# H15R00.net
KiCad netlist of a schematic drawn in EAGLE
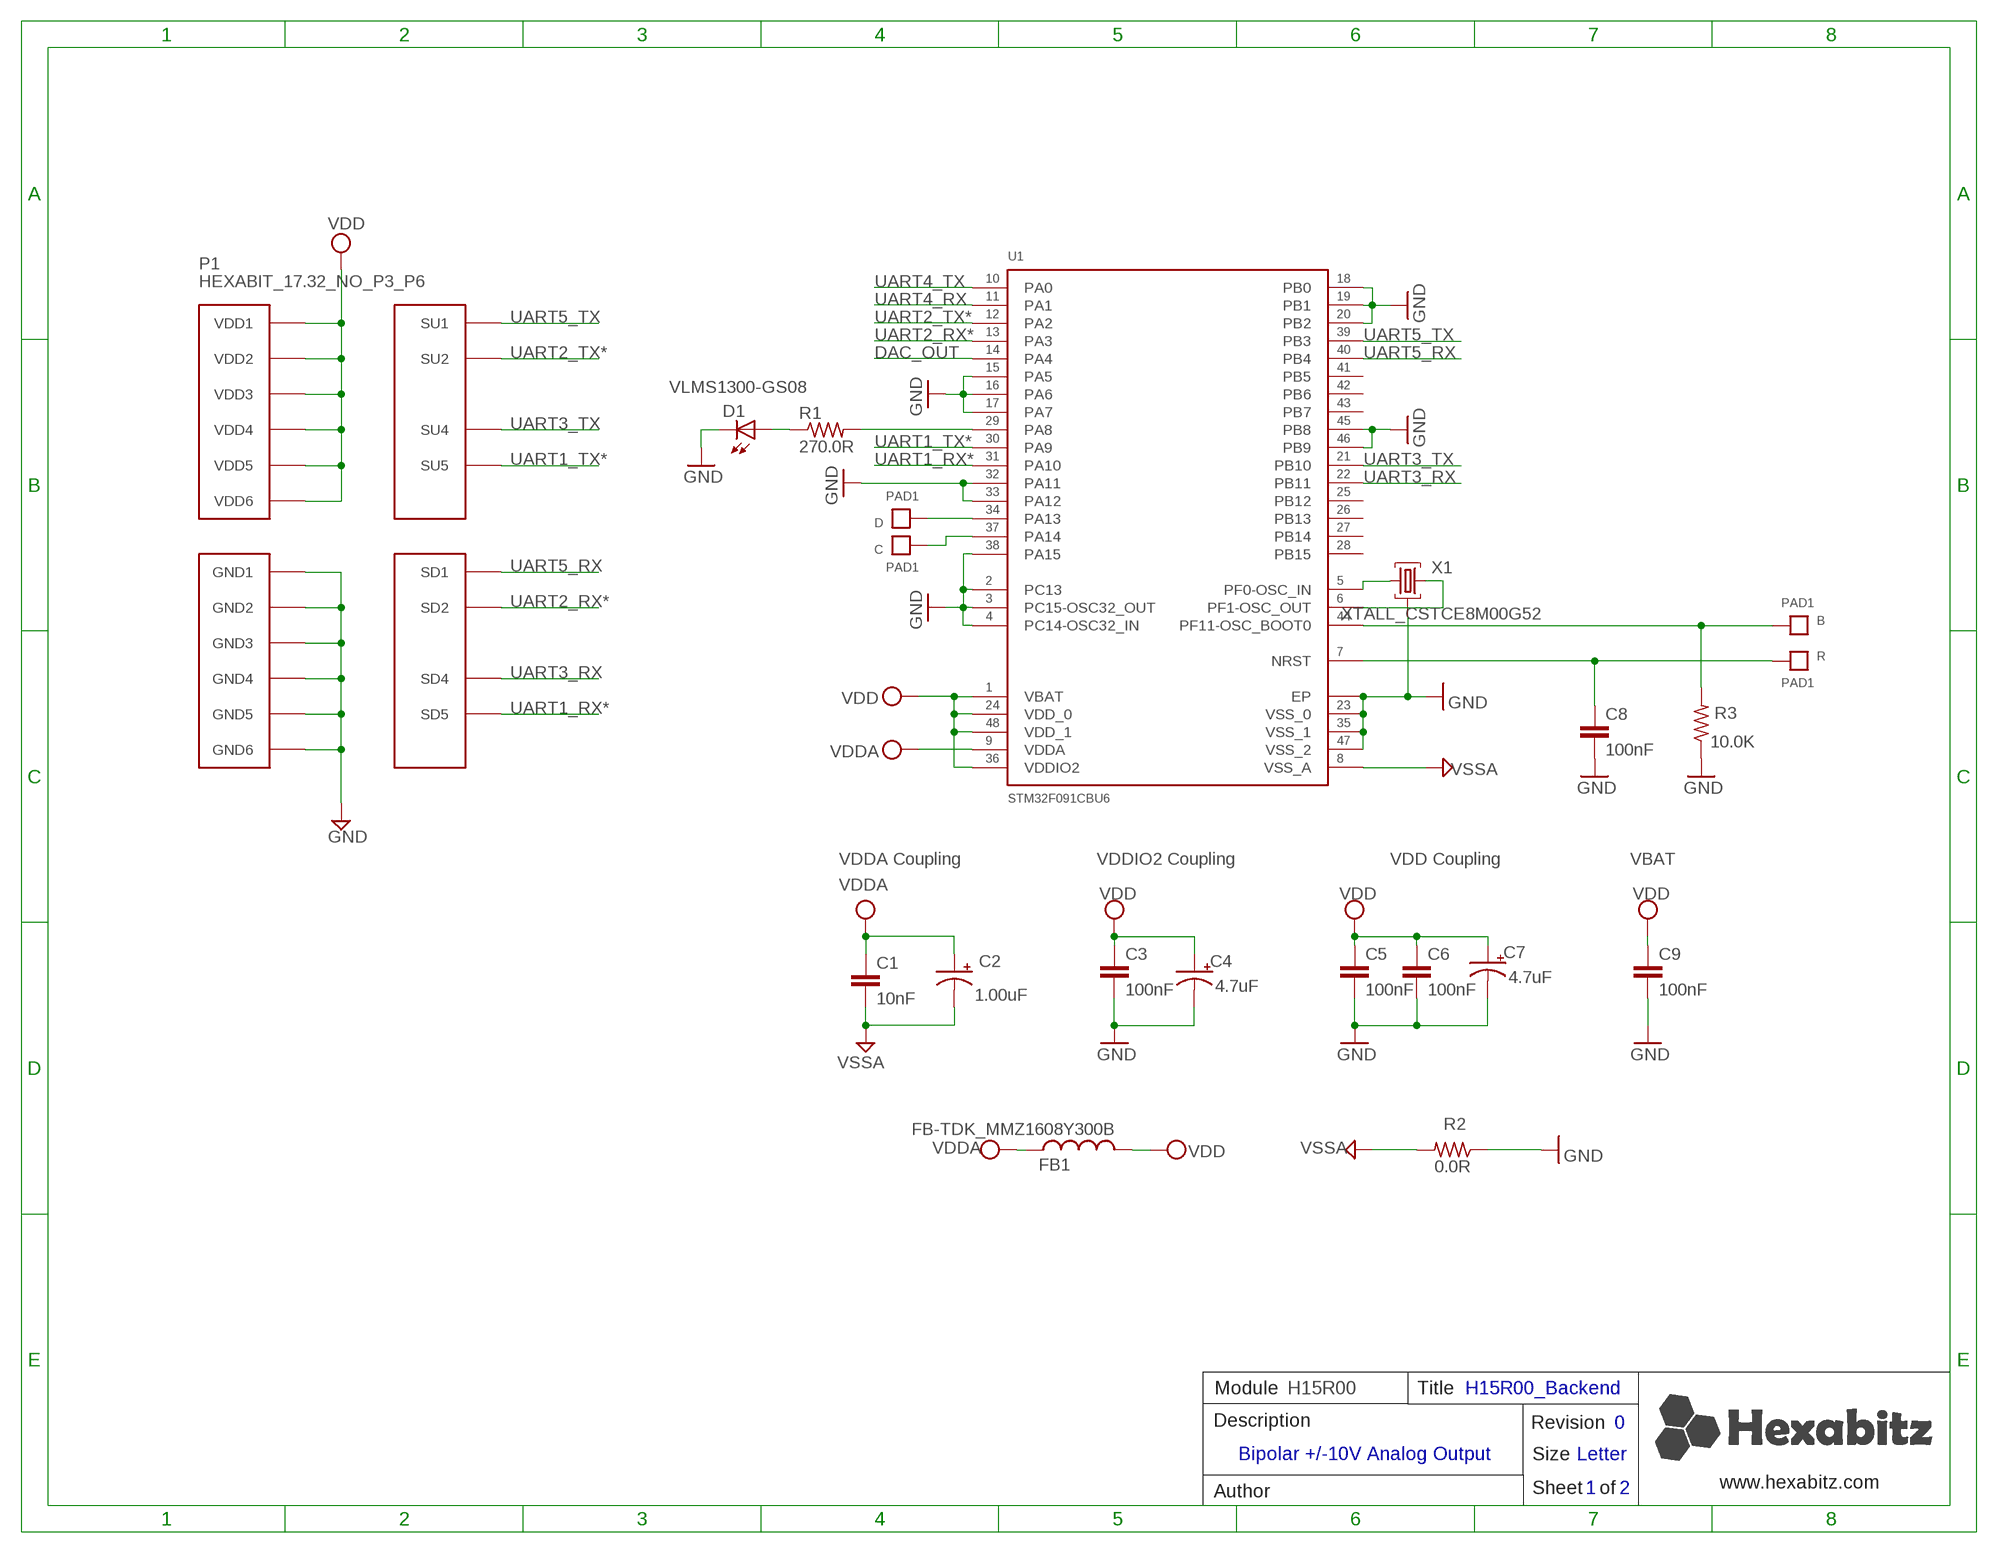
[diagram p0: schematic, sheet 1]
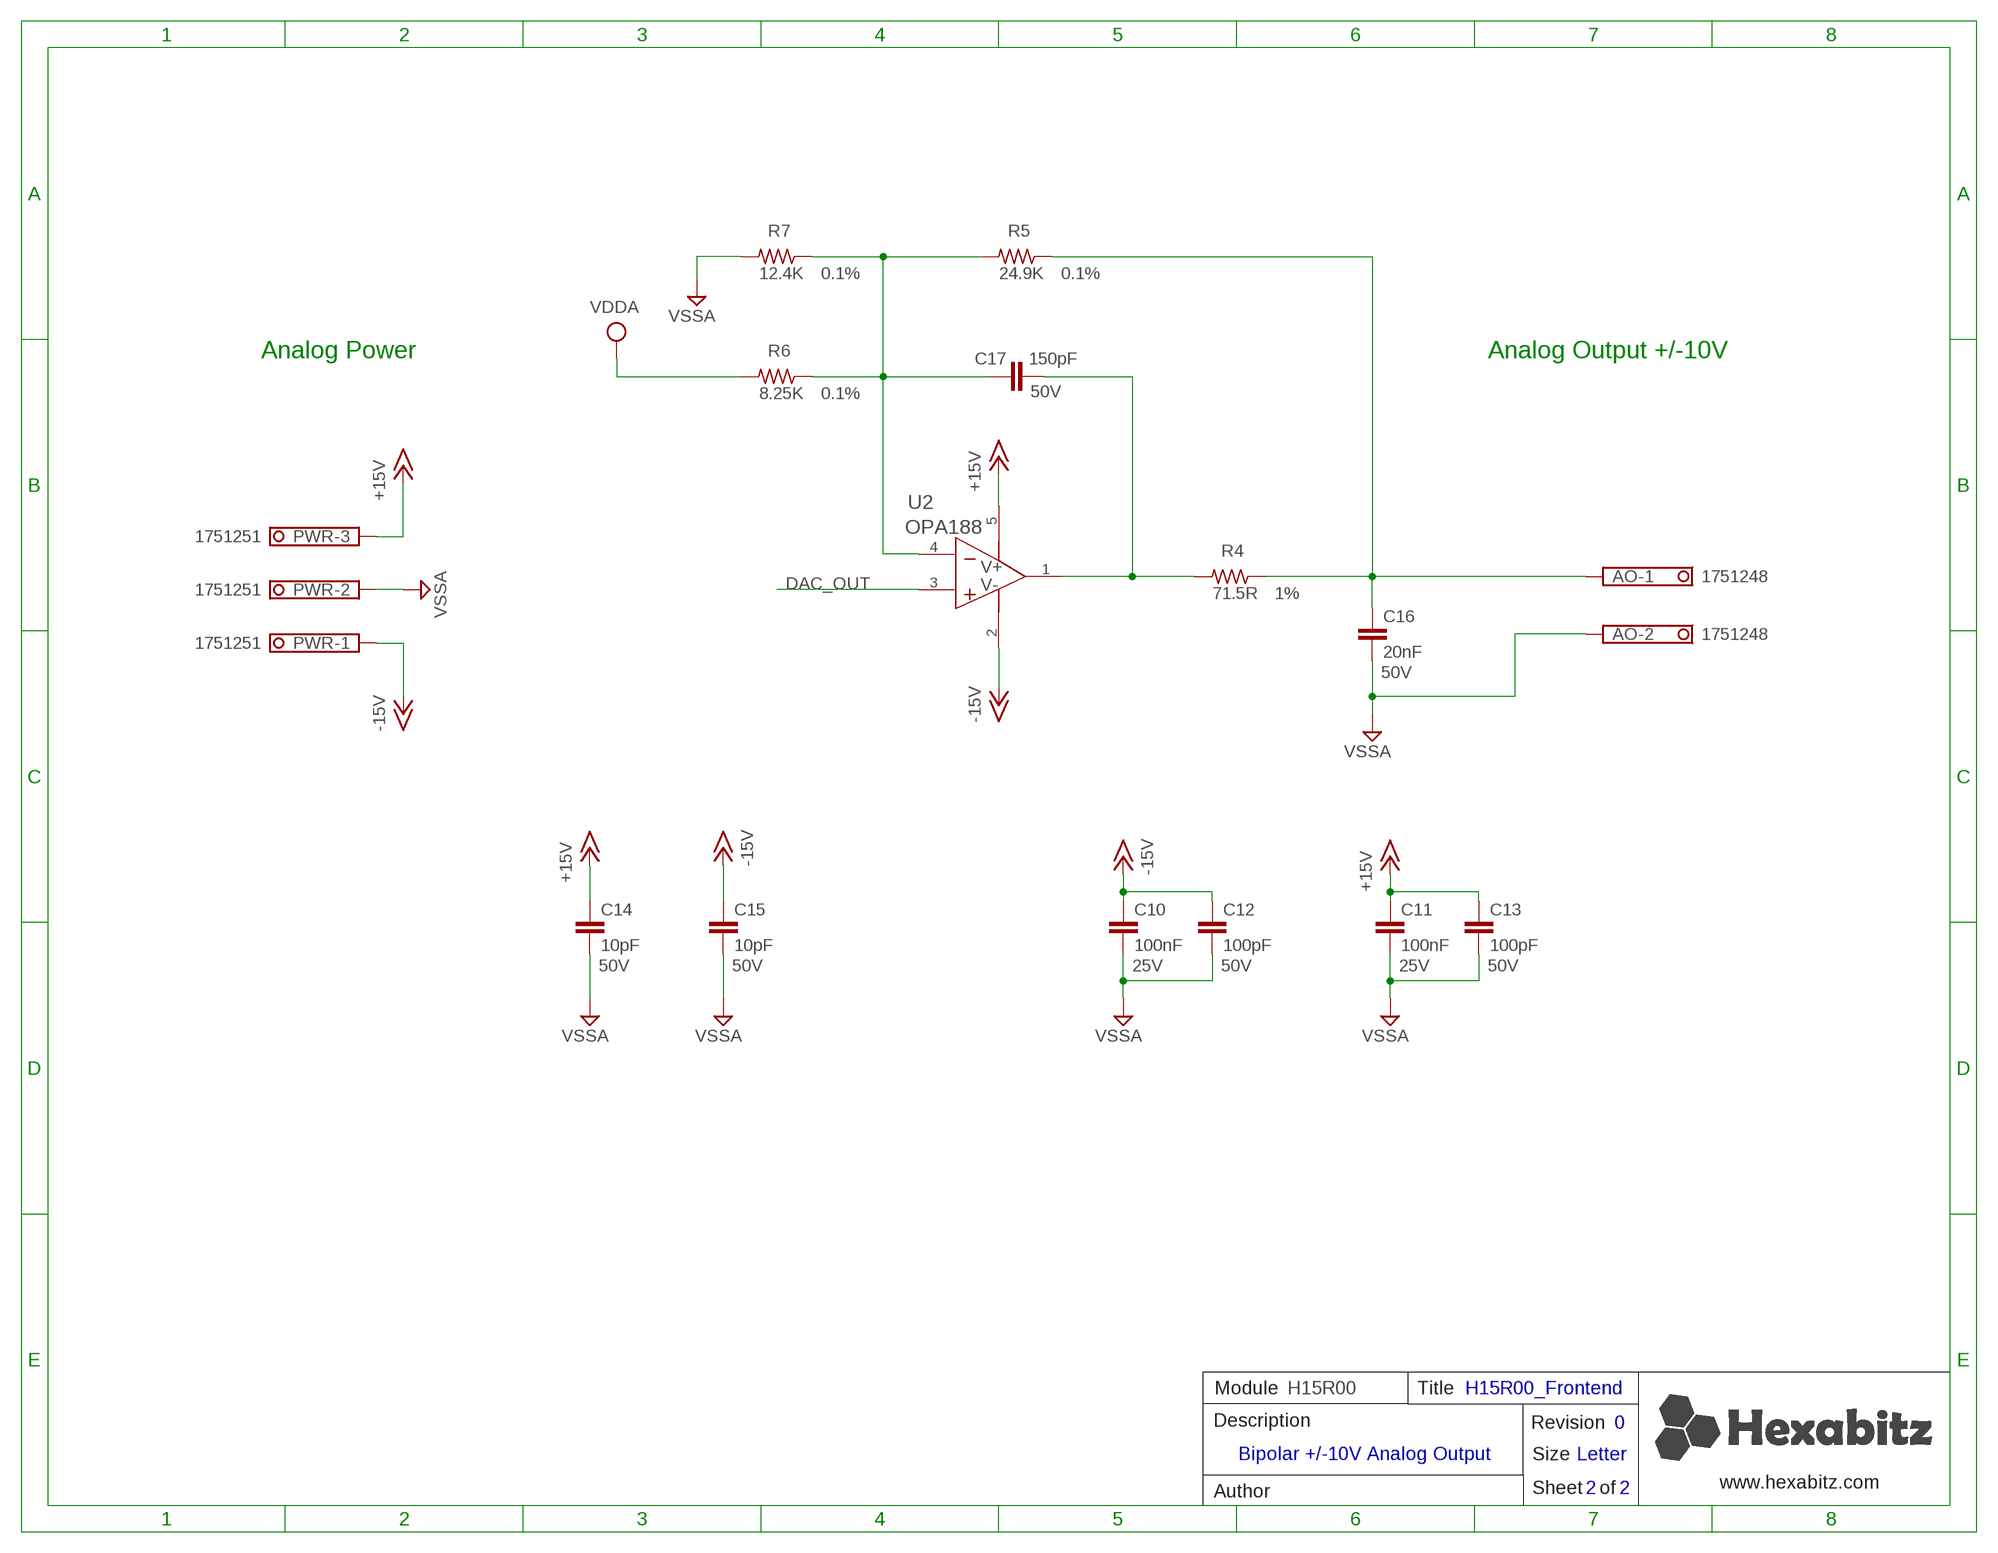
[diagram p1: schematic, sheet 2]

(export (version "E")
  (design (tool "Eeschema 10.0.6"))
  (components
    (comp (ref "AO")
      (value "1751248")
      (footprint "eagle-import:CON-PHOENIX-350_1751248")
      (fields
        (field (name "MPN") "1751248")
        (field (name "MFN") "Phoenix Contact")
        (field (name "OCTOPART_URL") "https://octopart.com/1751248-phoenix+contact-31334?r=sp&s=dfbEyNHiQNetUL69ahOrPQ")
      )
      (libsource (lib "eagle-import") (part "CON-PHOENIX-350_1751248"))
    )
    (comp (ref "C10")
      (value "100nF")
      (footprint "eagle-import:C-0603")
      (fields
        (field (name "CAPACITANCE") "100nF")
        (field (name "MFN") "Murata")
        (field (name "MPN") "GRM188R71E104KA01D")
        (field (name "OCTOPART_URL") "https://octopart.com/grm188r71e104ka01d-murata-196239?r=sp&s=9Sa0iYM-THq9pjXKXbxryA")
        (field (name "TOLERANCE") "10%")
        (field (name "VOLTAGE_RATING") "25V")
      )
      (libsource (lib "eagle-import") (part "C-0603"))
    )
    (comp (ref "C11")
      (value "100nF")
      (footprint "eagle-import:C-0603")
      (fields
        (field (name "CAPACITANCE") "100nF")
        (field (name "MFN") "Murata")
        (field (name "MPN") "GRM188R71E104KA01D")
        (field (name "OCTOPART_URL") "https://octopart.com/grm188r71e104ka01d-murata-196239?r=sp&s=9Sa0iYM-THq9pjXKXbxryA")
        (field (name "TOLERANCE") "10%")
        (field (name "VOLTAGE_RATING") "25V")
      )
      (libsource (lib "eagle-import") (part "C-0603"))
    )
    (comp (ref "C12")
      (value "100pF")
      (footprint "eagle-import:C-0603")
      (fields
        (field (name "CAPACITANCE") "100pF")
        (field (name "MFN") "Avx")
        (field (name "MPN") "06035A101JAT2A")
        (field (name "OCTOPART_URL") "https://octopart.com/06035a101jat2a-avx-55386344?r=sp&s=OWJQ2Zm8S2q0g8RSQtFoSw")
        (field (name "TOLERANCE") "5%")
        (field (name "VOLTAGE_RATING") "50V")
      )
      (libsource (lib "eagle-import") (part "C-0603"))
    )
    (comp (ref "C13")
      (value "100pF")
      (footprint "eagle-import:C-0603")
      (fields
        (field (name "CAPACITANCE") "100pF")
        (field (name "MFN") "Avx")
        (field (name "MPN") "06035A101JAT2A")
        (field (name "OCTOPART_URL") "https://octopart.com/06035a101jat2a-avx-55386344?r=sp&s=OWJQ2Zm8S2q0g8RSQtFoSw")
        (field (name "TOLERANCE") "5%")
        (field (name "VOLTAGE_RATING") "50V")
      )
      (libsource (lib "eagle-import") (part "C-0603"))
    )
    (comp (ref "C14")
      (value "10pF")
      (footprint "eagle-import:C-0603")
      (fields
        (field (name "CAPACITANCE") "10pF")
        (field (name "MFN") "Murata")
        (field (name "MPN") "GRM1885C1H100JA01D")
        (field (name "OCTOPART_URL") "https://octopart.com/grm1885c1h100ja01d-murata-196121?r=sp&s=M0doikvzQymn4ajEe0ihSw")
        (field (name "TOLERANCE") "5%")
        (field (name "VOLTAGE_RATING") "50V")
      )
      (libsource (lib "eagle-import") (part "C-0603"))
    )
    (comp (ref "C15")
      (value "10pF")
      (footprint "eagle-import:C-0603")
      (fields
        (field (name "CAPACITANCE") "10pF")
        (field (name "MFN") "Murata")
        (field (name "MPN") "GRM1885C1H100JA01D")
        (field (name "OCTOPART_URL") "https://octopart.com/grm1885c1h100ja01d-murata-196121?r=sp&s=M0doikvzQymn4ajEe0ihSw")
        (field (name "TOLERANCE") "5%")
        (field (name "VOLTAGE_RATING") "50V")
      )
      (libsource (lib "eagle-import") (part "C-0603"))
    )
    (comp (ref "C16")
      (value "20nF")
      (footprint "eagle-import:C-0603")
      (fields
        (field (name "CAPACITANCE") "20nF")
        (field (name "MFN") "Samsung")
        (field (name "MPN") "CL10B203KB8NNNC")
        (field (name "OCTOPART_URL") "https://octopart.com/cl10b203kb8nnnc-samsung-19831635?r=sp&s=OBY_pk9VR_mJ3Hxg4Ft1_g")
        (field (name "TOLERANCE") "10%")
        (field (name "VOLTAGE_RATING") "50V")
      )
      (libsource (lib "eagle-import") (part "C-0603"))
    )
    (comp (ref "C17")
      (value "150pF")
      (footprint "eagle-import:C-0603")
      (fields
        (field (name "CAPACITANCE") "150pF")
        (field (name "MFN") "TDK")
        (field (name "MPN") "C1608C0G1H151F080AA")
        (field (name "OCTOPART_URL") "https://octopart.com/c1608c0g1h151f080aa-tdk-26013419?r=sp&s=gUiTfpbJT1mAyA8NJ0XI8Q")
        (field (name "TOLERANCE") "1%")
        (field (name "VOLTAGE_RATING") "50V")
      )
      (libsource (lib "eagle-import") (part "C-0603"))
    )
    (comp (ref "PWR")
      (value "1751251")
      (footprint "eagle-import:1751251")
      (fields
        (field (name "MPN") "1751251")
        (field (name "MFN") "Phoenix Contact")
        (field (name "OCTOPART_URL") "https://octopart.com/1751251-phoenix+contact-36473?r=sp&s=9M0VWNoHTyq04j3qI6lQOQ")
      )
      (libsource (lib "eagle-import") (part "1751251"))
    )
    (comp (ref "R4")
      (value "71.5R")
      (footprint "eagle-import:R-0603")
      (fields
        (field (name "MFN") "Panasonic")
        (field (name "MPN") "ERJ-3EKF71R5V")
        (field (name "OCTOPART_URL") "https://octopart.com/erj-3ekf71r5v-panasonic-55421901?r=sp&s=JXFkVIq0Td2PcEUj2-UrKA")
        (field (name "RESISTANCE") "71.5 Ohm")
        (field (name "TOLERANCE") "1%")
      )
      (libsource (lib "eagle-import") (part "R-0603"))
    )
    (comp (ref "R5")
      (value "24.9K")
      (footprint "eagle-import:R-0603")
      (fields
        (field (name "MFN") "Panasonic")
        (field (name "MPN") "ERA-3AEB2492V")
        (field (name "OCTOPART_URL") "https://octopart.com/era-3aeb2492v-panasonic-14412272?r=sp&s=tIguNO2DQ02PU7gq6_vEIQ")
        (field (name "RESISTANCE") "24.9 kOhm")
        (field (name "TOLERANCE") "0.1%")
      )
      (libsource (lib "eagle-import") (part "R-0603"))
    )
    (comp (ref "R6")
      (value "8.25K")
      (footprint "eagle-import:R-0603")
      (fields
        (field (name "MFN") "Panasonic")
        (field (name "MPN") "ERA-3AEB8251V")
        (field (name "OCTOPART_URL") "https://octopart.com/era-3aeb8251v-panasonic-55477301?r=sp&s=p46abNa6QO-wGnrush-PUA")
        (field (name "RESISTANCE") "8.25 kOhm")
        (field (name "TOLERANCE") "0.1%")
      )
      (libsource (lib "eagle-import") (part "R-0603"))
    )
    (comp (ref "R7")
      (value "12.4K")
      (footprint "eagle-import:R-0603")
      (fields
        (field (name "MFN") "Panasonic")
        (field (name "MPN") "ERA-3AEB1242V")
        (field (name "OCTOPART_URL") "https://octopart.com/era-3aeb1242v-panasonic-55639351?r=sp&s=K0xQjqOwSGaT1tqbXnh0hg")
        (field (name "RESISTANCE") "12.4 kOhm")
        (field (name "TOLERANCE") "0.1%")
      )
      (libsource (lib "eagle-import") (part "R-0603"))
    )
    (comp (ref "U2")
      (value "OPA188")
      (footprint "eagle-import:DBV0005A_N")
      (fields
        (field (name "ALTERNATE_PARTNUMBER") "OPA188AIDBVT")
        (field (name "MANUFACTURER") "Texas Instruments")
        (field (name "MPN") "OPA188AIDBVR")
      )
      (libsource (lib "eagle-import") (part "OPA188AIDBVR"))
    )
    (comp (ref "B")
      (value "PAD1")
      (footprint "eagle-import:PAD1")
      (libsource (lib "eagle-import") (part "PAD1"))
    )
    (comp (ref "C")
      (value "PAD1")
      (footprint "eagle-import:PAD1")
      (libsource (lib "eagle-import") (part "PAD1"))
    )
    (comp (ref "C1")
      (value "10nF")
      (footprint "eagle-import:C-0603")
      (fields
        (field (name "CAPACITANCE") "10nF")
        (field (name "MFN") "KEMET")
        (field (name "MPN") "C0603C103K5RACTU")
        (field (name "OCTOPART_URL") "https://octopart.com/c0603c103k5ractu-kemet-133094?r=sp&s=R_iPBxLnSmGqhkU2rIMFpg")
        (field (name "TOLERANCE") "10%")
        (field (name "VOLTAGE_RATING") "50V")
      )
      (libsource (lib "eagle-import") (part "C-0603"))
    )
    (comp (ref "C2")
      (value "1.00uF")
      (footprint "eagle-import:C-0805-POL")
      (fields
        (field (name "CAPACITANCE") "1.00uF")
        (field (name "MFN") "Yageo")
        (field (name "MPN") "CC0805KKX7R7BB105")
        (field (name "OCTOPART_URL") "https://octopart.com/cc0805kkx7r7bb105-yageo-8376555?r=sp&s=YKl1wwtkROau_X5nniH2ig")
        (field (name "TOLERANCE") "10%")
        (field (name "VOLTAGE_RATING") "16V")
      )
      (libsource (lib "eagle-import") (part "C-0805-POL"))
    )
    (comp (ref "C3")
      (value "100nF")
      (footprint "eagle-import:C-0603")
      (fields
        (field (name "CAPACITANCE") "100nF")
        (field (name "MFN") "KEMET")
        (field (name "MPN") "C0603C104K8RACTU")
        (field (name "OCTOPART_URL") "https://octopart.com/c0603c104k8ractu-kemet-145075?r=sp&s=9bS9ASSwSEqMCE9KBEQZ0g")
        (field (name "TOLERANCE") "10%")
        (field (name "VOLTAGE_RATING") "10V")
      )
      (libsource (lib "eagle-import") (part "C-0603"))
    )
    (comp (ref "C4")
      (value "4.7uF")
      (footprint "eagle-import:C-0805-POL")
      (fields
        (field (name "CAPACITANCE") "4.7uF")
        (field (name "MFN") "Murata")
        (field (name "MPN") "GRM21BC81E475KA12L")
        (field (name "OCTOPART_URL") "https://octopart.com/grm21bc81e475ka12l-murata-10331911?r=sp&s=RY3qZSD8T6mG6TC9CHI5qQ")
        (field (name "TOLERANCE") "10%")
        (field (name "VOLTAGE_RATING") "25V")
      )
      (libsource (lib "eagle-import") (part "C-0805-POL"))
    )
    (comp (ref "C5")
      (value "100nF")
      (footprint "eagle-import:C-0603")
      (fields
        (field (name "CAPACITANCE") "100nF")
        (field (name "MFN") "KEMET")
        (field (name "MPN") "C0603C104K8RACTU")
        (field (name "OCTOPART_URL") "https://octopart.com/c0603c104k8ractu-kemet-145075?r=sp&s=9bS9ASSwSEqMCE9KBEQZ0g")
        (field (name "TOLERANCE") "10%")
        (field (name "VOLTAGE_RATING") "10")
      )
      (libsource (lib "eagle-import") (part "C-0603"))
    )
    (comp (ref "C6")
      (value "100nF")
      (footprint "eagle-import:C-0603")
      (fields
        (field (name "CAPACITANCE") "100nF")
        (field (name "MFN") "KEMET")
        (field (name "MPN") "C0603C104K8RACTU")
        (field (name "OCTOPART_URL") "https://octopart.com/c0603c104k8ractu-kemet-145075?r=sp&s=9bS9ASSwSEqMCE9KBEQZ0g")
        (field (name "TOLERANCE") "10%")
        (field (name "VOLTAGE_RATING") "10V")
      )
      (libsource (lib "eagle-import") (part "C-0603"))
    )
    (comp (ref "C7")
      (value "4.7uF")
      (footprint "eagle-import:C-0805-POL")
      (fields
        (field (name "CAPACITANCE") "4.7uF")
        (field (name "MFN") "Murata")
        (field (name "MPN") "GRM21BC81E475KA12L")
        (field (name "OCTOPART_URL") "https://octopart.com/grm21bc81e475ka12l-murata-10331911?r=sp&s=RY3qZSD8T6mG6TC9CHI5qQ")
        (field (name "TOLERANCE") "10%")
        (field (name "VOLTAGE_RATING") "25V")
      )
      (libsource (lib "eagle-import") (part "C-0805-POL"))
    )
    (comp (ref "C8")
      (value "100nF")
      (footprint "eagle-import:C-0603")
      (fields
        (field (name "CAPACITANCE") "100nF")
        (field (name "MFN") "KEMET")
        (field (name "MPN") "C0603C104K8RACTU")
        (field (name "OCTOPART_URL") "https://octopart.com/c0603c104k8ractu-kemet-145075?r=sp&s=9bS9ASSwSEqMCE9KBEQZ0g")
        (field (name "TOLERANCE") "10%")
        (field (name "VOLTAGE_RATING") "10V")
      )
      (libsource (lib "eagle-import") (part "C-0603"))
    )
    (comp (ref "C9")
      (value "100nF")
      (footprint "eagle-import:C-0603")
      (fields
        (field (name "CAPACITANCE") "100nF")
        (field (name "MFN") "KEMET")
        (field (name "MPN") "C0603C104K8RACTU")
        (field (name "OCTOPART_URL") "https://octopart.com/c0603c104k8ractu-kemet-145075?r=sp&s=9bS9ASSwSEqMCE9KBEQZ0g")
        (field (name "TOLERANCE") "10V")
        (field (name "VOLTAGE_RATING") "10%")
      )
      (libsource (lib "eagle-import") (part "C-0603"))
    )
    (comp (ref "D")
      (value "PAD1")
      (footprint "eagle-import:PAD1")
      (libsource (lib "eagle-import") (part "PAD1"))
    )
    (comp (ref "D1")
      (value "VLMS1300-GS08")
      (footprint "eagle-import:VLMS1300-GS08")
      (fields
        (field (name "MFN") "Vishay")
        (field (name "MPN") "VLMS1300-GS08")
        (field (name "OCTOPART_URL") "https://octopart.com/vlms1300-gs08-vishay-21709201?r=sp&s=_gcP4_q8T1SC6PJQPTQ9yA")
      )
      (libsource (lib "eagle-import") (part "VLMS1300-GS08"))
    )
    (comp (ref "FB1")
      (value "FB-TDK_MMZ1608Y300B")
      (footprint "eagle-import:FB-TDK_MMZ1608Y300B")
      (fields
        (field (name "MFN") "TDK ")
        (field (name "MPN") "MMZ1608Y300B")
        (field (name "OCTOPART_URL") "https://octopart.com/mmz1608y300b-tdk-368280?r=sp&s=cd9_2ZEqQ9q9UNBuQgHAiA")
      )
      (libsource (lib "eagle-import") (part "FB-TDK_MMZ1608Y300B"))
    )
    (comp (ref "P1")
      (value "HEXABIT_17.32_NO_P3_P6")
      (footprint "eagle-import:HEXABIT_17.32_NO_P3_P6")
      (libsource (lib "eagle-import") (part "HEXABIT_?_NO_P3_P617.32"))
    )
    (comp (ref "R")
      (value "PAD1")
      (footprint "eagle-import:PAD1")
      (libsource (lib "eagle-import") (part "PAD1"))
    )
    (comp (ref "R1")
      (value "270.0R")
      (footprint "eagle-import:R-0603")
      (fields
        (field (name "MFN") "Yageo")
        (field (name "MPN") "RC0603FR-07270RL")
        (field (name "OCTOPART_URL") "https://octopart.com/search?q=RC0603FR-07270RL&start=0")
        (field (name "RESISTANCE") "270.0 Ohm")
        (field (name "TOLERANCE") "1%")
      )
      (libsource (lib "eagle-import") (part "R-0603"))
    )
    (comp (ref "R2")
      (value "0.0R")
      (footprint "eagle-import:R-0603")
      (fields
        (field (name "MFN") "Yageo")
        (field (name "MPN") "RC0603JR-070RL")
        (field (name "OCTOPART_URL") "https://octopart.com/rc0603jr-070rl-yageo-1241539?r=sp&s=X2NteqRjRNWrnx42Y0aliA")
        (field (name "RESISTANCE") "0.0 Ohm")
      )
      (libsource (lib "eagle-import") (part "R-0603"))
    )
    (comp (ref "R3")
      (value "10.0K")
      (footprint "eagle-import:R-0603")
      (fields
        (field (name "MFN") "Yageo")
        (field (name "MPN") "RC0603JR-0710KL")
        (field (name "OCTOPART_URL") "https://octopart.com/search?q=RC0603JR-0710KL&start=0")
        (field (name "RESISTANCE") "10.0K Ohm")
        (field (name "TOLERANCE") "5%")
      )
      (libsource (lib "eagle-import") (part "R-0603"))
    )
    (comp (ref "U1")
      (value "STM32F091CBU6")
      (footprint "eagle-import:STM32F091CBU6")
      (libsource (lib "eagle-import") (part "STM32F091CBU6"))
    )
    (comp (ref "X1")
      (value "XTALL_CSTCE8M00G52")
      (footprint "eagle-import:XTALL_CSTCE8M00G52")
      (fields (field (name "MPN") "CSTCE8M00G52Z-R0"))
      (libsource (lib "eagle-import") (part "XTALL_CSTCE8M00G52"))
    )
  )
  (nets
    (net (code "1") (name "+15V") (class "Default")
      (node (ref "C11") (pin "1") (pinfunction "1_1") (pintype "passive"))
      (node (ref "C13") (pin "1") (pinfunction "1_1") (pintype "passive"))
      (node (ref "C14") (pin "1") (pinfunction "1_1") (pintype "passive"))
      (node (ref "PWR") (pin "3") (pinfunction "K_3") (pintype "passive"))
      (node (ref "U2") (pin "5") (pinfunction "V+_5") (pintype "power_in"))
    )
    (net (code "2") (name "-15V") (class "Default")
      (node (ref "C10") (pin "1") (pinfunction "1_1") (pintype "passive"))
      (node (ref "C12") (pin "1") (pinfunction "1_1") (pintype "passive"))
      (node (ref "C15") (pin "1") (pinfunction "1_1") (pintype "passive"))
      (node (ref "PWR") (pin "1") (pinfunction "K_1") (pintype "passive"))
      (node (ref "U2") (pin "2") (pinfunction "V-_2") (pintype "power_in"))
    )
    (net (code "3") (name "DAC_OUT") (class "Default")
      (node (ref "U1") (pin "P$14") (pinfunction "PA4_P$14") (pintype "bidirectional"))
      (node (ref "U2") (pin "3") (pinfunction "IN+_3") (pintype "input"))
    )
    (net (code "4") (name "GND") (class "Default")
      (node (ref "C3") (pin "2") (pinfunction "2_2") (pintype "passive"))
      (node (ref "C4") (pin "2") (pinfunction "-_2") (pintype "passive"))
      (node (ref "C5") (pin "2") (pinfunction "2_2") (pintype "passive"))
      (node (ref "C6") (pin "2") (pinfunction "2_2") (pintype "passive"))
      (node (ref "C7") (pin "2") (pinfunction "-_2") (pintype "passive"))
      (node (ref "C8") (pin "2") (pinfunction "2_2") (pintype "passive"))
      (node (ref "C9") (pin "2") (pinfunction "2_2") (pintype "passive"))
      (node (ref "D1") (pin "C") (pinfunction "C_C") (pintype "passive"))
      (node (ref "P1") (pin "PAD_PD10") (pinfunction "GND4_PAD_PD10") (pintype "power_in"))
      (node (ref "P1") (pin "PAD_PD11") (pinfunction "GND5_PAD_PD11") (pintype "power_in"))
      (node (ref "P1") (pin "PAD_PD12") (pinfunction "GND6_PAD_PD12") (pintype "power_in"))
      (node (ref "P1") (pin "PAD_PD7") (pinfunction "GND1_PAD_PD7") (pintype "power_in"))
      (node (ref "P1") (pin "PAD_PD8") (pinfunction "GND2_PAD_PD8") (pintype "power_in"))
      (node (ref "P1") (pin "PAD_PD9") (pinfunction "GND3_PAD_PD9") (pintype "power_in"))
      (node (ref "R2") (pin "1") (pinfunction "1_1") (pintype "passive"))
      (node (ref "R3") (pin "1") (pinfunction "1_1") (pintype "passive"))
      (node (ref "U1") (pin "EP") (pinfunction "EP_EP") (pintype "power_in"))
      (node (ref "U1") (pin "P$15") (pinfunction "PA5_P$15") (pintype "bidirectional"))
      (node (ref "U1") (pin "P$16") (pinfunction "PA6_P$16") (pintype "bidirectional"))
      (node (ref "U1") (pin "P$17") (pinfunction "PA7_P$17") (pintype "bidirectional"))
      (node (ref "U1") (pin "P$18") (pinfunction "PB0_P$18") (pintype "bidirectional"))
      (node (ref "U1") (pin "P$19") (pinfunction "PB1_P$19") (pintype "bidirectional"))
      (node (ref "U1") (pin "P$2") (pinfunction "PC13_P$2") (pintype "bidirectional"))
      (node (ref "U1") (pin "P$20") (pinfunction "PB2_P$20") (pintype "bidirectional"))
      (node (ref "U1") (pin "P$23") (pinfunction "VSS_0_P$23") (pintype "power_in"))
      (node (ref "U1") (pin "P$3") (pinfunction "PC14-OSC32_IN_P$3") (pintype "bidirectional"))
      (node (ref "U1") (pin "P$32") (pinfunction "PA11_P$32") (pintype "bidirectional"))
      (node (ref "U1") (pin "P$33") (pinfunction "PA12_P$33") (pintype "bidirectional"))
      (node (ref "U1") (pin "P$35") (pinfunction "VSS_1_P$35") (pintype "power_in"))
      (node (ref "U1") (pin "P$38") (pinfunction "PA15_P$38") (pintype "bidirectional"))
      (node (ref "U1") (pin "P$4") (pinfunction "PC15-OSC32_OUT_P$4") (pintype "bidirectional"))
      (node (ref "U1") (pin "P$45") (pinfunction "PB8_P$45") (pintype "bidirectional"))
      (node (ref "U1") (pin "P$46") (pinfunction "PB9_P$46") (pintype "bidirectional"))
      (node (ref "U1") (pin "P$47") (pinfunction "VSS_2_P$47") (pintype "power_in"))
      (node (ref "X1") (pin "P$2") (pinfunction "2_P$2") (pintype "passive"))
    )
    (net (code "5") (name "Net-(AOA-K)") (class "Default")
      (node (ref "AO") (pin "1") (pinfunction "K_1") (pintype "passive"))
      (node (ref "C16") (pin "1") (pinfunction "1_1") (pintype "passive"))
      (node (ref "R4") (pin "1") (pinfunction "1_1") (pintype "passive"))
      (node (ref "R5") (pin "1") (pinfunction "1_1") (pintype "passive"))
    )
    (net (code "6") (name "Net-(D1-PadA)") (class "Default")
      (node (ref "D1") (pin "A") (pinfunction "A_A") (pintype "passive"))
      (node (ref "R1") (pin "1") (pinfunction "1_1") (pintype "passive"))
    )
    (net (code "7") (name "Net-(U1-NRST)") (class "Default")
      (node (ref "C8") (pin "1") (pinfunction "1_1") (pintype "passive"))
      (node (ref "R") (pin "P$1") (pinfunction "P$1_P$1") (pintype "passive"))
      (node (ref "R") (pin "P$2") (pinfunction "P$1_P$2") (pintype "passive"))
      (node (ref "U1") (pin "P$7") (pinfunction "NRST_P$7") (pintype "passive"))
    )
    (net (code "8") (name "Net-(U1-PA8)") (class "Default")
      (node (ref "R1") (pin "2") (pinfunction "2_2") (pintype "passive"))
      (node (ref "U1") (pin "P$29") (pinfunction "PA8_P$29") (pintype "bidirectional"))
    )
    (net (code "9") (name "Net-(U1-PA13)") (class "Default")
      (node (ref "D") (pin "P$1") (pinfunction "P$1_P$1") (pintype "passive"))
      (node (ref "D") (pin "P$2") (pinfunction "P$1_P$2") (pintype "passive"))
      (node (ref "U1") (pin "P$34") (pinfunction "PA13_P$34") (pintype "bidirectional"))
    )
    (net (code "10") (name "Net-(U1-PA14)") (class "Default")
      (node (ref "C") (pin "P$1") (pinfunction "P$1_P$1") (pintype "passive"))
      (node (ref "C") (pin "P$2") (pinfunction "P$1_P$2") (pintype "passive"))
      (node (ref "U1") (pin "P$37") (pinfunction "PA14_P$37") (pintype "bidirectional"))
    )
    (net (code "11") (name "Net-(U1-PF0-OSC_IN)") (class "Default")
      (node (ref "U1") (pin "P$5") (pinfunction "PF0-OSC_IN_P$5") (pintype "bidirectional"))
      (node (ref "X1") (pin "P$1") (pinfunction "1_P$1") (pintype "passive"))
    )
    (net (code "12") (name "Net-(U1-PF1-OSC_OUT)") (class "Default")
      (node (ref "U1") (pin "P$6") (pinfunction "PF1-OSC_OUT_P$6") (pintype "bidirectional"))
      (node (ref "X1") (pin "P$3") (pinfunction "3_P$3") (pintype "passive"))
    )
    (net (code "13") (name "Net-(U1-PF11-OSC_BOOT0)") (class "Default")
      (node (ref "B") (pin "P$1") (pinfunction "P$1_P$1") (pintype "passive"))
      (node (ref "B") (pin "P$2") (pinfunction "P$1_P$2") (pintype "passive"))
      (node (ref "R3") (pin "2") (pinfunction "2_2") (pintype "passive"))
      (node (ref "U1") (pin "P$44") (pinfunction "PF11-OSC_BOOT0_P$44") (pintype "bidirectional"))
    )
    (net (code "14") (name "Net-(U2-IN-)") (class "Default")
      (node (ref "C17") (pin "1") (pinfunction "1_1") (pintype "passive"))
      (node (ref "R5") (pin "2") (pinfunction "2_2") (pintype "passive"))
      (node (ref "R6") (pin "1") (pinfunction "1_1") (pintype "passive"))
      (node (ref "R7") (pin "1") (pinfunction "1_1") (pintype "passive"))
      (node (ref "U2") (pin "4") (pinfunction "IN-_4") (pintype "input"))
    )
    (net (code "15") (name "Net-(U2-OUT)") (class "Default")
      (node (ref "C17") (pin "2") (pinfunction "2_2") (pintype "passive"))
      (node (ref "R4") (pin "2") (pinfunction "2_2") (pintype "passive"))
      (node (ref "U2") (pin "1") (pinfunction "OUT_1") (pintype "output"))
    )
    (net (code "16") (name "UART1_RX*") (class "Default")
      (node (ref "P1") (pin "PAD_PD5") (pinfunction "SD5_PAD_PD5") (pintype "bidirectional"))
      (node (ref "U1") (pin "P$31") (pinfunction "PA10_P$31") (pintype "bidirectional"))
    )
    (net (code "17") (name "UART1_TX*") (class "Default")
      (node (ref "P1") (pin "PAD_PU5") (pinfunction "SU5_PAD_PU5") (pintype "bidirectional"))
      (node (ref "U1") (pin "P$30") (pinfunction "PA9_P$30") (pintype "bidirectional"))
    )
    (net (code "18") (name "UART2_RX*") (class "Default")
      (node (ref "P1") (pin "PAD_PD2") (pinfunction "SD2_PAD_PD2") (pintype "bidirectional"))
      (node (ref "U1") (pin "P$13") (pinfunction "PA3_P$13") (pintype "bidirectional"))
    )
    (net (code "19") (name "UART2_TX*") (class "Default")
      (node (ref "P1") (pin "PAD_PU2") (pinfunction "SU2_PAD_PU2") (pintype "bidirectional"))
      (node (ref "U1") (pin "P$12") (pinfunction "PA2_P$12") (pintype "bidirectional"))
    )
    (net (code "20") (name "UART3_RX") (class "Default")
      (node (ref "P1") (pin "PAD_PD4") (pinfunction "SD4_PAD_PD4") (pintype "bidirectional"))
      (node (ref "U1") (pin "P$22") (pinfunction "PB11_P$22") (pintype "bidirectional"))
    )
    (net (code "21") (name "UART3_TX") (class "Default")
      (node (ref "P1") (pin "PAD_PU4") (pinfunction "SU4_PAD_PU4") (pintype "bidirectional"))
      (node (ref "U1") (pin "P$21") (pinfunction "PB10_P$21") (pintype "bidirectional"))
    )
    (net (code "22") (name "UART4_RX") (class "Default")
      (node (ref "U1") (pin "P$11") (pinfunction "PA1_P$11") (pintype "bidirectional"))
    )
    (net (code "23") (name "UART4_TX") (class "Default")
      (node (ref "U1") (pin "P$10") (pinfunction "PA0_P$10") (pintype "bidirectional"))
    )
    (net (code "24") (name "UART5_RX") (class "Default")
      (node (ref "P1") (pin "PAD_PD1") (pinfunction "SD1_PAD_PD1") (pintype "bidirectional"))
      (node (ref "U1") (pin "P$40") (pinfunction "PB4_P$40") (pintype "bidirectional"))
    )
    (net (code "25") (name "UART5_TX") (class "Default")
      (node (ref "P1") (pin "PAD_PU1") (pinfunction "SU1_PAD_PU1") (pintype "bidirectional"))
      (node (ref "U1") (pin "P$39") (pinfunction "PB3_P$39") (pintype "bidirectional"))
    )
    (net (code "26") (name "VDD") (class "Default")
      (node (ref "C3") (pin "1") (pinfunction "1_1") (pintype "passive"))
      (node (ref "C4") (pin "1") (pinfunction "+_1") (pintype "passive"))
      (node (ref "C5") (pin "1") (pinfunction "1_1") (pintype "passive"))
      (node (ref "C6") (pin "1") (pinfunction "1_1") (pintype "passive"))
      (node (ref "C7") (pin "1") (pinfunction "+_1") (pintype "passive"))
      (node (ref "C9") (pin "1") (pinfunction "1_1") (pintype "passive"))
      (node (ref "FB1") (pin "2") (pinfunction "2_2") (pintype "passive"))
      (node (ref "P1") (pin "PAD_PU10") (pinfunction "VDD4_PAD_PU10") (pintype "power_in"))
      (node (ref "P1") (pin "PAD_PU11") (pinfunction "VDD5_PAD_PU11") (pintype "power_in"))
      (node (ref "P1") (pin "PAD_PU12") (pinfunction "VDD6_PAD_PU12") (pintype "power_in"))
      (node (ref "P1") (pin "PAD_PU7") (pinfunction "VDD1_PAD_PU7") (pintype "power_in"))
      (node (ref "P1") (pin "PAD_PU8") (pinfunction "VDD2_PAD_PU8") (pintype "power_in"))
      (node (ref "P1") (pin "PAD_PU9") (pinfunction "VDD3_PAD_PU9") (pintype "power_in"))
      (node (ref "U1") (pin "P$1") (pinfunction "VBAT_P$1") (pintype "power_in"))
      (node (ref "U1") (pin "P$24") (pinfunction "VDD_0_P$24") (pintype "power_in"))
      (node (ref "U1") (pin "P$36") (pinfunction "VDDIO2_P$36") (pintype "power_in"))
      (node (ref "U1") (pin "P$48") (pinfunction "VDD_1_P$48") (pintype "power_in"))
    )
    (net (code "27") (name "VDDA") (class "Default")
      (node (ref "C1") (pin "1") (pinfunction "1_1") (pintype "passive"))
      (node (ref "C2") (pin "1") (pinfunction "+_1") (pintype "passive"))
      (node (ref "FB1") (pin "1") (pinfunction "1_1") (pintype "passive"))
      (node (ref "R6") (pin "2") (pinfunction "2_2") (pintype "passive"))
      (node (ref "U1") (pin "P$9") (pinfunction "VDDA_P$9") (pintype "power_in"))
    )
    (net (code "28") (name "VSSA") (class "Default")
      (node (ref "AO") (pin "2") (pinfunction "K_2") (pintype "passive"))
      (node (ref "C1") (pin "2") (pinfunction "2_2") (pintype "passive"))
      (node (ref "C10") (pin "2") (pinfunction "2_2") (pintype "passive"))
      (node (ref "C11") (pin "2") (pinfunction "2_2") (pintype "passive"))
      (node (ref "C12") (pin "2") (pinfunction "2_2") (pintype "passive"))
      (node (ref "C13") (pin "2") (pinfunction "2_2") (pintype "passive"))
      (node (ref "C14") (pin "2") (pinfunction "2_2") (pintype "passive"))
      (node (ref "C15") (pin "2") (pinfunction "2_2") (pintype "passive"))
      (node (ref "C16") (pin "2") (pinfunction "2_2") (pintype "passive"))
      (node (ref "C2") (pin "2") (pinfunction "-_2") (pintype "passive"))
      (node (ref "PWR") (pin "2") (pinfunction "K_2") (pintype "passive"))
      (node (ref "R2") (pin "2") (pinfunction "2_2") (pintype "passive"))
      (node (ref "R7") (pin "2") (pinfunction "2_2") (pintype "passive"))
      (node (ref "U1") (pin "P$8") (pinfunction "VSS_A_P$8") (pintype "power_in"))
    )
    (net (code "29") (name "unconnected-(U1-PB5-PadP$41)") (class "Default")
      (node (ref "U1") (pin "P$41") (pinfunction "PB5_P$41") (pintype "bidirectional"))
    )
    (net (code "30") (name "unconnected-(U1-PB6-PadP$42)") (class "Default")
      (node (ref "U1") (pin "P$42") (pinfunction "PB6_P$42") (pintype "bidirectional"))
    )
    (net (code "31") (name "unconnected-(U1-PB7-PadP$43)") (class "Default")
      (node (ref "U1") (pin "P$43") (pinfunction "PB7_P$43") (pintype "bidirectional"))
    )
    (net (code "32") (name "unconnected-(U1-PB12-PadP$25)") (class "Default")
      (node (ref "U1") (pin "P$25") (pinfunction "PB12_P$25") (pintype "bidirectional"))
    )
    (net (code "33") (name "unconnected-(U1-PB13-PadP$26)") (class "Default")
      (node (ref "U1") (pin "P$26") (pinfunction "PB13_P$26") (pintype "bidirectional"))
    )
    (net (code "34") (name "unconnected-(U1-PB14-PadP$27)") (class "Default")
      (node (ref "U1") (pin "P$27") (pinfunction "PB14_P$27") (pintype "bidirectional"))
    )
    (net (code "35") (name "unconnected-(U1-PB15-PadP$28)") (class "Default")
      (node (ref "U1") (pin "P$28") (pinfunction "PB15_P$28") (pintype "bidirectional"))
    )
  )
)
